# Esp32.net
KiCad netlist of a schematic drawn in Altium Designer
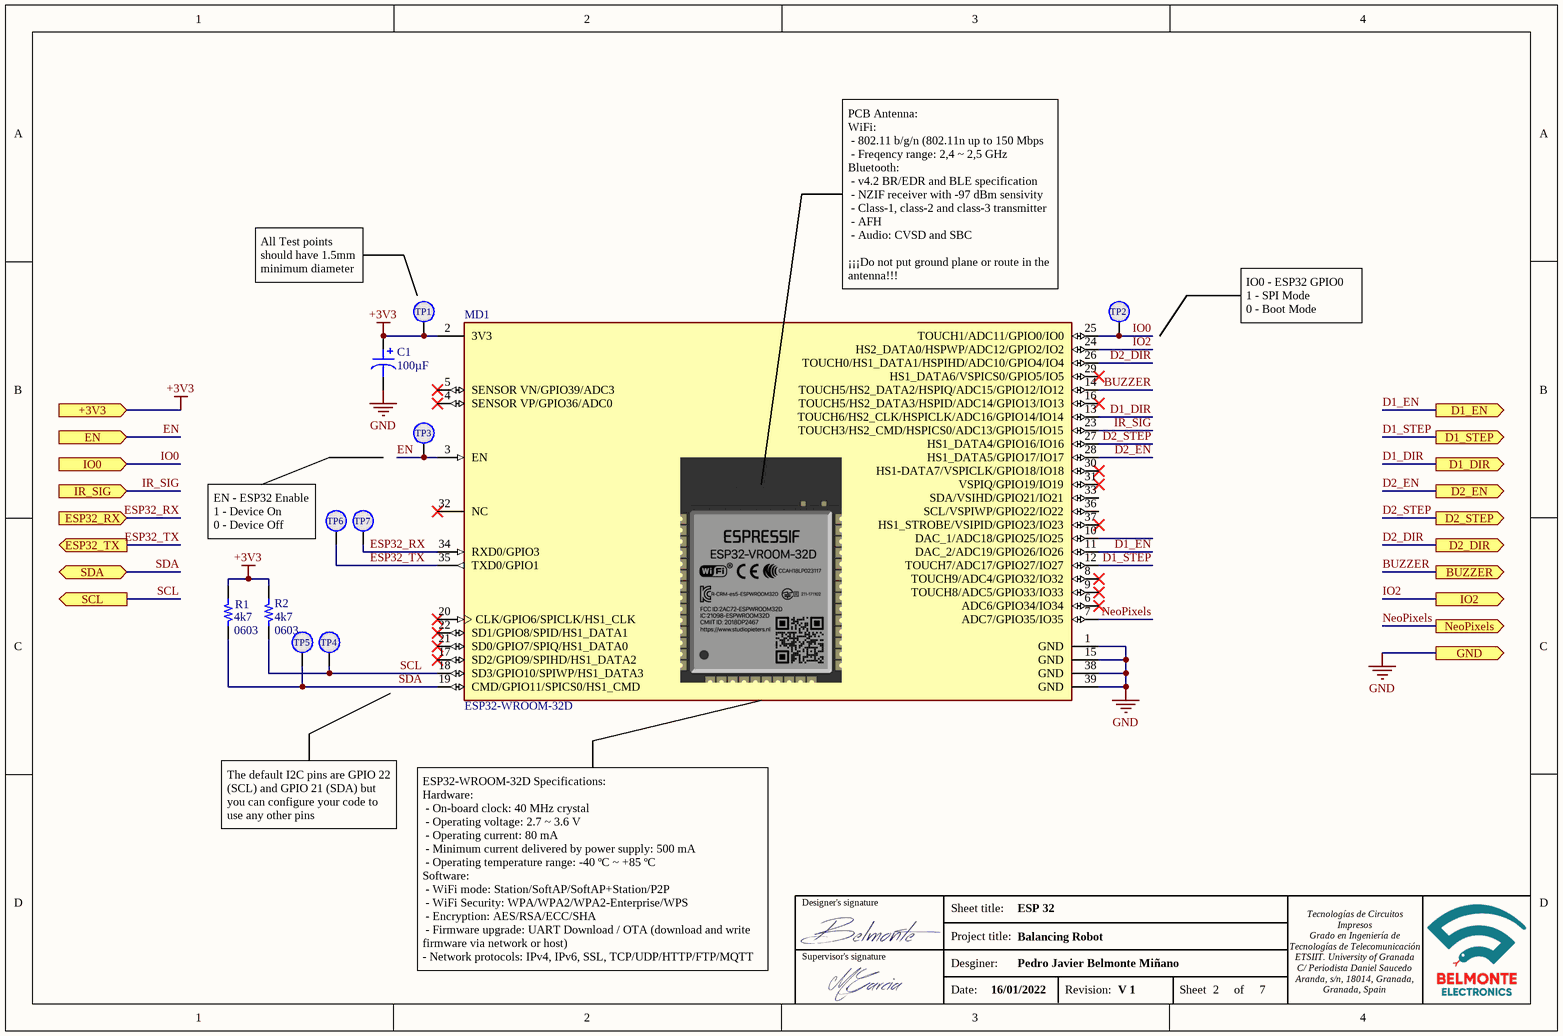
[diagram p0: Esp32.SchDoc]

(export (version "E")
  (design (tool "Eeschema 10.0.6"))
  (components
    (comp (ref "C1")
      (value "ALUM 100uF")
      (footprint "CAP ALSMD POLY 5.3MM H6.1MM")
      (description "CAP ALUM 100UF 4V 2000H")
      (fields
        (field (name "PART NUMBER") "MAL218497352E3")
        (field (name "MANUFACTURER") "Vishay Beyschlag/Draloric/BC Components")
        (field (name "CAPACITANCE") "100µF")
      )
      (libsource (lib "ControlBoard") (part "MAL218497352E3"))
    )
    (comp (ref "MD1")
      (value "ESP32-WROOM-32D")
      (footprint "FP-ESP32-WROOM-32D-MFG")
      (description "WIFI MODULE 32MBITS SPI FLASH")
      (fields
        (field (name "OCTOPART") "https://octopart.com/esp32-wroom-32d-espressif+systems-91040050")
        (field (name "MANUFACTURER") "Espressif Systems")
      )
      (libsource (lib "ControlBoard") (part "CMP-194065-000003-1"))
    )
    (comp (ref "R1")
      (value "4k7")
      (footprint "RESC1608X55X30NL15T15")
      (fields
        (field (name "TOLERANCE") "5%")
        (field (name "MANUFACTURER") "Vishay Dale")
        (field (name "MANUFACTURER PART NUMBER") "CRCW06034K70FKEB")
        (field (name "SIZE") "0603")
      )
      (libsource (lib "ControlBoard") (part "CMP-1012-00586-3"))
    )
    (comp (ref "R2")
      (value "4k7")
      (footprint "RESC1608X55X30NL15T15")
      (fields
        (field (name "TOLERANCE") "5%")
        (field (name "MANUFACTURER") "Vishay Dale")
        (field (name "MANUFACTURER PART NUMBER") "CRCW06034K70FKEB")
        (field (name "SIZE") "0603")
      )
      (libsource (lib "ControlBoard") (part "CMP-1012-00586-3"))
    )
    (comp (ref "TP1")
      (value "Test point")
      (footprint "TestPoint")
      (libsource (lib "ControlBoard") (part "TestPoint"))
    )
    (comp (ref "TP2")
      (value "Test point")
      (footprint "TestPoint")
      (libsource (lib "ControlBoard") (part "TestPoint"))
    )
    (comp (ref "TP3")
      (value "Test point")
      (footprint "TestPoint")
      (libsource (lib "ControlBoard") (part "TestPoint"))
    )
    (comp (ref "TP4")
      (value "Test point")
      (footprint "TestPoint")
      (libsource (lib "ControlBoard") (part "TestPoint"))
    )
    (comp (ref "TP5")
      (value "Test point")
      (footprint "TestPoint")
      (libsource (lib "ControlBoard") (part "TestPoint"))
    )
    (comp (ref "TP6")
      (value "Test point")
      (footprint "TestPoint")
      (libsource (lib "ControlBoard") (part "TestPoint"))
    )
    (comp (ref "TP7")
      (value "Test point")
      (footprint "TestPoint")
      (libsource (lib "ControlBoard") (part "TestPoint"))
    )
  )
  (nets
    (net (code "1") (name "+3V3") (class "Default")
      (node (ref "C1") (pin "1") (pinfunction "1_1") (pintype "passive"))
      (node (ref "MD1") (pin "2") (pinfunction "3V3_2") (pintype "power_in"))
      (node (ref "R1") (pin "1") (pinfunction "1_1") (pintype "passive"))
      (node (ref "R2") (pin "1") (pinfunction "1_1") (pintype "passive"))
      (node (ref "TP1") (pin "1") (pinfunction "_1_1") (pintype "passive"))
    )
    (net (code "2") (name "/BUZZER") (class "Default")
      (node (ref "MD1") (pin "14") (pinfunction "TOUCH5/HS2_DATA2/HSPIQ/ADC15/GPIO12/IO12_14") (pintype "bidirectional"))
    )
    (net (code "3") (name "/D1_DIR") (class "Default")
      (node (ref "MD1") (pin "13") (pinfunction "TOUCH6/HS2_CLK/HSPICLK/ADC16/GPIO14/IO14_13") (pintype "bidirectional"))
    )
    (net (code "4") (name "/D1_EN") (class "Default")
      (node (ref "MD1") (pin "11") (pinfunction "DAC_2/ADC19/GPIO26/IO26_11") (pintype "bidirectional"))
    )
    (net (code "5") (name "/D1_STEP") (class "Default")
      (node (ref "MD1") (pin "12") (pinfunction "TOUCH7/ADC17/GPIO27/IO27_12") (pintype "bidirectional"))
    )
    (net (code "6") (name "/D2_DIR") (class "Default")
      (node (ref "MD1") (pin "26") (pinfunction "TOUCH0/HS1_DATA1/HSPIHD/ADC10/GPIO4/IO4_26") (pintype "bidirectional"))
    )
    (net (code "7") (name "/D2_EN") (class "Default")
      (node (ref "MD1") (pin "28") (pinfunction "HS1_DATA5/GPIO17/IO17_28") (pintype "bidirectional"))
    )
    (net (code "8") (name "/D2_STEP") (class "Default")
      (node (ref "MD1") (pin "27") (pinfunction "HS1_DATA4/GPIO16/IO16_27") (pintype "bidirectional"))
    )
    (net (code "9") (name "/EN") (class "Default")
      (node (ref "MD1") (pin "3") (pinfunction "EN_3") (pintype "input"))
      (node (ref "TP3") (pin "1") (pinfunction "_1_1") (pintype "passive"))
    )
    (net (code "10") (name "/ESP32_RX") (class "Default")
      (node (ref "MD1") (pin "34") (pinfunction "RXD0/GPIO3_34") (pintype "input"))
      (node (ref "TP7") (pin "1") (pinfunction "_1_1") (pintype "passive"))
    )
    (net (code "11") (name "/ESP32_TX") (class "Default")
      (node (ref "MD1") (pin "35") (pinfunction "TXD0/GPIO1_35") (pintype "output"))
      (node (ref "TP6") (pin "1") (pinfunction "_1_1") (pintype "passive"))
    )
    (net (code "12") (name "/IO0") (class "Default")
      (node (ref "MD1") (pin "25") (pinfunction "TOUCH1/ADC11/GPIO0/IO0_25") (pintype "bidirectional"))
      (node (ref "TP2") (pin "1") (pinfunction "_1_1") (pintype "passive"))
    )
    (net (code "13") (name "/IO2") (class "Default")
      (node (ref "MD1") (pin "24") (pinfunction "HS2_DATA0/HSPWP/ADC12/GPIO2/IO2_24") (pintype "bidirectional"))
    )
    (net (code "14") (name "/IR_SIG") (class "Default")
      (node (ref "MD1") (pin "23") (pinfunction "TOUCH3/HS2_CMD/HSPICS0/ADC13/GPIO15/IO15_23") (pintype "bidirectional"))
    )
    (net (code "15") (name "/NeoPixels") (class "Default")
      (node (ref "MD1") (pin "7") (pinfunction "ADC7/GPIO35/IO35_7") (pintype "bidirectional"))
    )
    (net (code "16") (name "/SCL") (class "Default")
      (node (ref "MD1") (pin "18") (pinfunction "SD3/GPIO10/SPIWP/HS1_DATA3_18") (pintype "bidirectional"))
      (node (ref "R2") (pin "2") (pinfunction "2_2") (pintype "passive"))
      (node (ref "TP4") (pin "1") (pinfunction "_1_1") (pintype "passive"))
    )
    (net (code "17") (name "/SDA") (class "Default")
      (node (ref "MD1") (pin "19") (pinfunction "CMD/GPIO11/SPICS0/HS1_CMD_19") (pintype "bidirectional"))
      (node (ref "R1") (pin "2") (pinfunction "2_2") (pintype "passive"))
      (node (ref "TP5") (pin "1") (pinfunction "_1_1") (pintype "passive"))
    )
    (net (code "18") (name "GND") (class "Default")
      (node (ref "C1") (pin "2") (pinfunction "2_2") (pintype "passive"))
      (node (ref "MD1") (pin "1") (pinfunction "GND_1") (pintype "power_in"))
      (node (ref "MD1") (pin "15") (pinfunction "GND_15") (pintype "power_in"))
      (node (ref "MD1") (pin "38") (pinfunction "GND_38") (pintype "power_in"))
      (node (ref "MD1") (pin "39") (pinfunction "GND_39") (pintype "power_in"))
    )
    (net (code "19") (name "unconnected-(MD1-ADC6{slash}GPIO34{slash}IO34-Pad6)") (class "Default")
      (node (ref "MD1") (pin "6") (pinfunction "ADC6/GPIO34/IO34_6") (pintype "bidirectional+no_connect"))
    )
    (net (code "20") (name "unconnected-(MD1-CLK{slash}GPIO6{slash}SPICLK{slash}HS1_CLK-Pad20)") (class "Default")
      (node (ref "MD1") (pin "20") (pinfunction "CLK/GPIO6/SPICLK/HS1_CLK_20") (pintype "input+no_connect"))
    )
    (net (code "21") (name "unconnected-(MD1-DAC_1{slash}ADC18{slash}GPIO25{slash}IO25-Pad10)") (class "Default")
      (node (ref "MD1") (pin "10") (pinfunction "DAC_1/ADC18/GPIO25/IO25_10") (pintype "bidirectional"))
    )
    (net (code "22") (name "unconnected-(MD1-HS1-DATA7{slash}VSPICLK{slash}GPIO18{slash}IO18-Pad30)") (class "Default")
      (node (ref "MD1") (pin "30") (pinfunction "HS1-DATA7/VSPICLK/GPIO18/IO18_30") (pintype "bidirectional+no_connect"))
    )
    (net (code "23") (name "unconnected-(MD1-HS1_DATA6{slash}VSPICS0{slash}GPIO5{slash}IO5-Pad29)") (class "Default")
      (node (ref "MD1") (pin "29") (pinfunction "HS1_DATA6/VSPICS0/GPIO5/IO5_29") (pintype "bidirectional+no_connect"))
    )
    (net (code "24") (name "unconnected-(MD1-HS1_STROBE{slash}VSIPID{slash}GPIO23{slash}IO23-Pad37)") (class "Default")
      (node (ref "MD1") (pin "37") (pinfunction "HS1_STROBE/VSIPID/GPIO23/IO23_37") (pintype "bidirectional+no_connect"))
    )
    (net (code "25") (name "unconnected-(MD1-NC-Pad32)") (class "Default")
      (node (ref "MD1") (pin "32") (pinfunction "NC_32") (pintype "passive+no_connect"))
    )
    (net (code "26") (name "unconnected-(MD1-SCL{slash}VSPIWP{slash}GPIO22{slash}IO22-Pad36)") (class "Default")
      (node (ref "MD1") (pin "36") (pinfunction "SCL/VSPIWP/GPIO22/IO22_36") (pintype "bidirectional"))
    )
    (net (code "27") (name "unconnected-(MD1-SD0{slash}GPIO7{slash}SPIQ{slash}HS1_DATA0-Pad21)") (class "Default")
      (node (ref "MD1") (pin "21") (pinfunction "SD0/GPIO7/SPIQ/HS1_DATA0_21") (pintype "bidirectional+no_connect"))
    )
    (net (code "28") (name "unconnected-(MD1-SD1{slash}GPIO8{slash}SPID{slash}HS1_DATA1-Pad22)") (class "Default")
      (node (ref "MD1") (pin "22") (pinfunction "SD1/GPIO8/SPID/HS1_DATA1_22") (pintype "bidirectional+no_connect"))
    )
    (net (code "29") (name "unconnected-(MD1-SD2{slash}GPIO9{slash}SPIHD{slash}HS1_DATA2-Pad17)") (class "Default")
      (node (ref "MD1") (pin "17") (pinfunction "SD2/GPIO9/SPIHD/HS1_DATA2_17") (pintype "bidirectional+no_connect"))
    )
    (net (code "30") (name "unconnected-(MD1-SDA{slash}VSIHD{slash}GPIO21{slash}IO21-Pad33)") (class "Default")
      (node (ref "MD1") (pin "33") (pinfunction "SDA/VSIHD/GPIO21/IO21_33") (pintype "bidirectional"))
    )
    (net (code "31") (name "unconnected-(MD1-SENSOR_VN{slash}GPIO39{slash}ADC3-Pad5)") (class "Default")
      (node (ref "MD1") (pin "5") (pinfunction "SENSOR_VN/GPIO39/ADC3_5") (pintype "bidirectional+no_connect"))
    )
    (net (code "32") (name "unconnected-(MD1-SENSOR_VP{slash}GPIO36{slash}ADC0-Pad4)") (class "Default")
      (node (ref "MD1") (pin "4") (pinfunction "SENSOR_VP/GPIO36/ADC0_4") (pintype "bidirectional+no_connect"))
    )
    (net (code "33") (name "unconnected-(MD1-TOUCH5{slash}HS2_DATA3{slash}HSPID{slash}ADC14{slash}GPIO13{slash}IO13-Pad16)") (class "Default")
      (node (ref "MD1") (pin "16") (pinfunction "TOUCH5/HS2_DATA3/HSPID/ADC14/GPIO13/IO13_16") (pintype "bidirectional+no_connect"))
    )
    (net (code "34") (name "unconnected-(MD1-TOUCH8{slash}ADC5{slash}GPIO33{slash}IO33-Pad9)") (class "Default")
      (node (ref "MD1") (pin "9") (pinfunction "TOUCH8/ADC5/GPIO33/IO33_9") (pintype "bidirectional+no_connect"))
    )
    (net (code "35") (name "unconnected-(MD1-TOUCH9{slash}ADC4{slash}GPIO32{slash}IO32-Pad8)") (class "Default")
      (node (ref "MD1") (pin "8") (pinfunction "TOUCH9/ADC4/GPIO32/IO32_8") (pintype "bidirectional+no_connect"))
    )
    (net (code "36") (name "unconnected-(MD1-VSPIQ{slash}GPIO19{slash}IO19-Pad31)") (class "Default")
      (node (ref "MD1") (pin "31") (pinfunction "VSPIQ/GPIO19/IO19_31") (pintype "bidirectional+no_connect"))
    )
  )
)
